# SCH_NERC_2025-07-13.net
KiCad netlist of a schematic drawn in EasyEDA
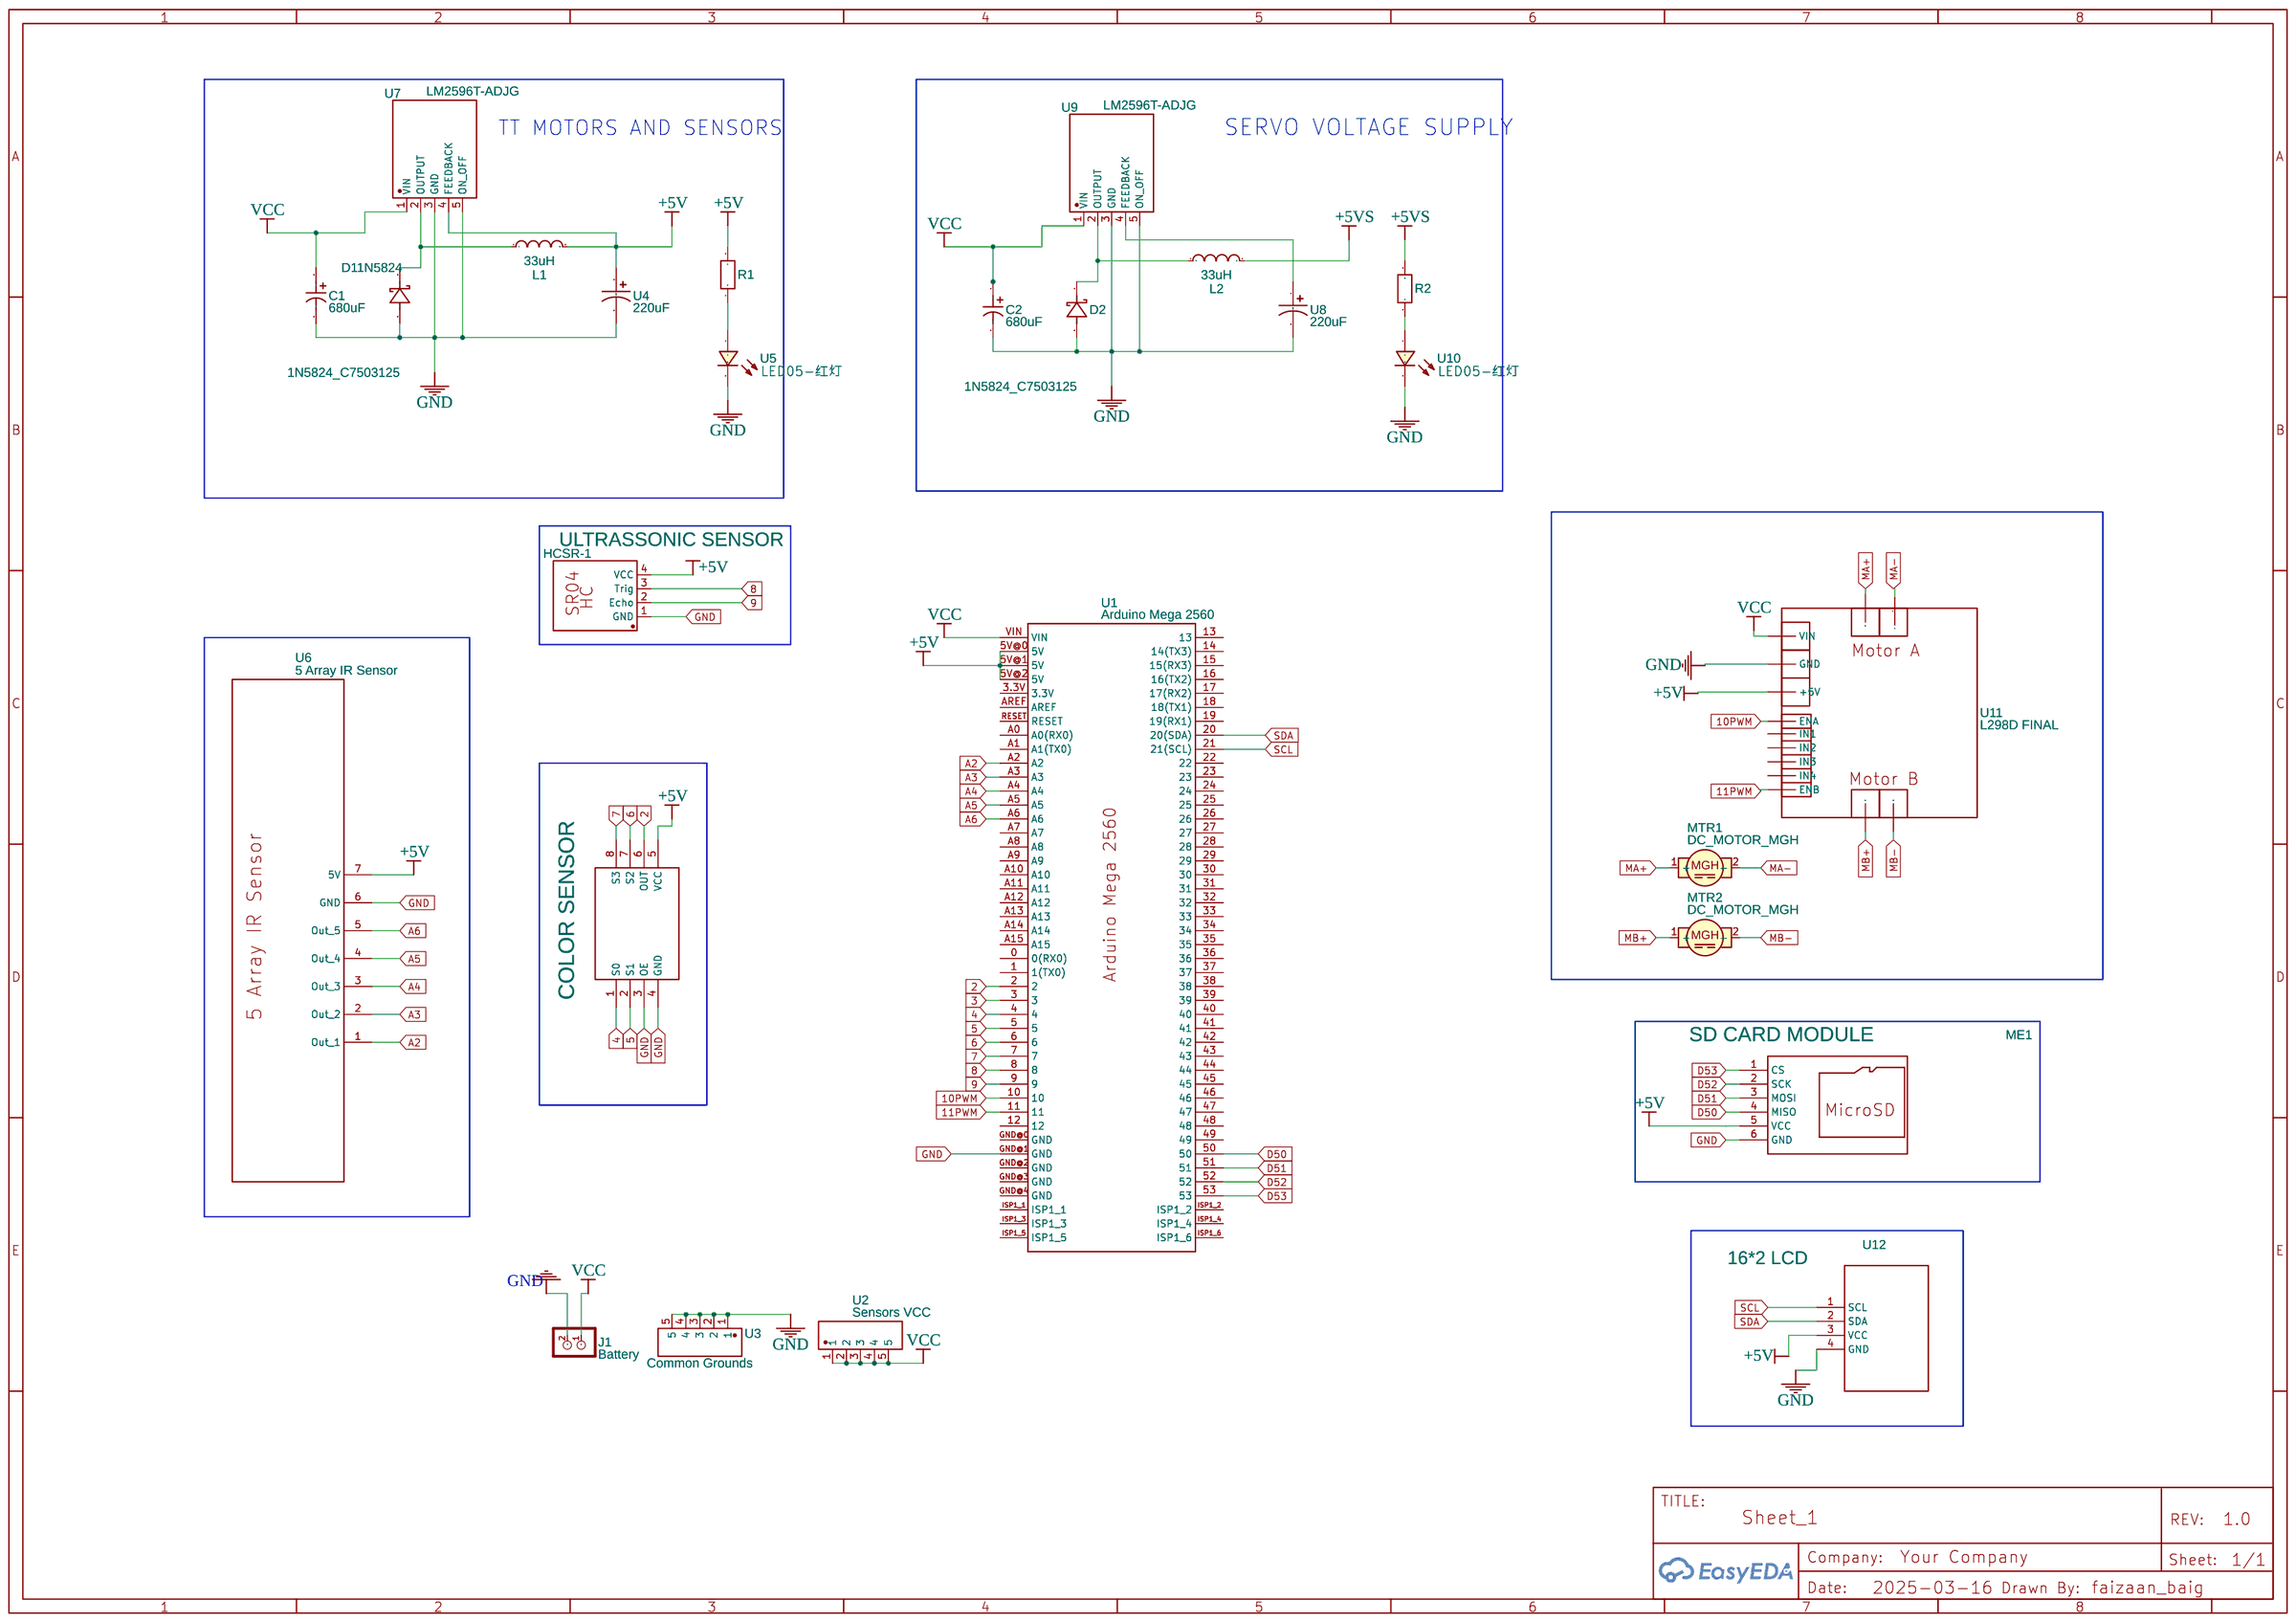
[diagram p0: schematic sheet]

(export (version "E")
  (design (tool "Eeschema 10.0.6"))
  (components
    (comp (ref "C1")
      (value "680uF")
      (fields
        (field (name "Manufacturer Part") "22UF400V87EC0285")
        (field (name "Manufacturer") "KNSCHA(科尼盛)")
      )
      (libsource (lib "") (part "22UF400V87EC0285"))
    )
    (comp (ref "C2")
      (value "680uF")
      (fields
        (field (name "Manufacturer Part") "22UF400V87EC0285")
        (field (name "Manufacturer") "KNSCHA(科尼盛)")
      )
      (libsource (lib "") (part "22UF400V87EC0285_1"))
    )
    (comp (ref "D2")
      (value "1N5824_C7503125")
      (fields (field (name "Manufacturer Part") "1N5824") (field (name "Manufacturer") "FUXINSEMI(富芯森美)"))
      (libsource (lib "") (part "1N5824_C7503125"))
    )
    (comp (ref "D11N5824")
      (value "1N5824_C7503125")
      (fields (field (name "Manufacturer Part") "1N5824") (field (name "Manufacturer") "FUXINSEMI(富芯森美)"))
      (libsource (lib "") (part "1N5824_C7503125_1"))
    )
    (comp (ref "HCSR-1") (value "ULTRASSONIC SENSOR") (libsource (lib "") (part "ULTRASSONIC SENSOR COPY")))
    (comp (ref "J1") (value "Battery") (libsource (lib "") (part "CON_TERMINAL_BLOCK_02-5MM")))
    (comp (ref "L1")
      (value "33uH")
      (fields (field (name "Manufacturer Part") "CKCS5040-33uH/M") (field (name "Manufacturer") "CENKER(岑科)"))
      (libsource (lib "") (part "CKCS5040-33UH/M_1"))
    )
    (comp (ref "L2")
      (value "33uH")
      (fields (field (name "Manufacturer Part") "CKCS5040-33uH/M") (field (name "Manufacturer") "CENKER(岑科)"))
      (libsource (lib "") (part "CKCS5040-33UH/M"))
    )
    (comp (ref "ME1")
      (value "SD CARD MODULE")
      (libsource (lib "") (part "CATALEX_MICRO_SD_CARD_MODULE_V1 SURYA"))
    )
    (comp (ref "MTR1") (value "DC_MOTOR_MGH") (libsource (lib "") (part "DC_MOTOR_MGH")))
    (comp (ref "MTR2") (value "DC_MOTOR_MGH") (libsource (lib "") (part "DC_MOTOR_MGH")))
    (comp (ref "R1")
      (value "贴片电阻CHIPRESISTORS")
      (fields (field (name "Manufacturer Part") "贴片电阻ChipResistors"))
      (libsource (lib "") (part "贴片电阻CHIPRESISTORS"))
    )
    (comp (ref "R2")
      (value "贴片电阻CHIPRESISTORS")
      (fields (field (name "Manufacturer Part") "贴片电阻ChipResistors"))
      (libsource (lib "") (part "贴片电阻CHIPRESISTORS"))
    )
    (comp (ref "SENSOR1") (value "COLOR SENSOR") (libsource (lib "") (part "COLOR SENSOR")))
    (comp (ref "U1") (value "Arduino Mega 2560") (libsource (lib "") (part "Arduino Mega 2560")))
    (comp (ref "U2")
      (value "Sensors VCC")
      (fields (field (name "Manufacturer Part") "HDR-1X5插件"))
      (libsource (lib "") (part "HDR-1X5."))
    )
    (comp (ref "U3")
      (value "Common Grounds")
      (fields (field (name "Manufacturer Part") "HDR-1X5插件"))
      (libsource (lib "") (part "HDR-1X5._1"))
    )
    (comp (ref "U4")
      (value "220uF")
      (fields
        (field (name "Manufacturer Part") "16YK220M6.3X11")
        (field (name "Manufacturer") "rubycon(红宝石)")
      )
      (libsource (lib "") (part "16YK220M6.3X11"))
    )
    (comp (ref "U5") (value "LED05-红灯") (libsource (lib "") (part "LED05-红灯")))
    (comp (ref "U6") (value "5 Array IR Sensor") (libsource (lib "") (part "5 Array IR Sensor")))
    (comp (ref "U7")
      (value "LM2596T-ADJG")
      (fields (field (name "Manufacturer") "HGC(深圳汉芯)"))
      (libsource (lib "") (part "LM2596T-ADJG"))
    )
    (comp (ref "U8")
      (value "220uF")
      (fields
        (field (name "Manufacturer Part") "16YK220M6.3X11")
        (field (name "Manufacturer") "rubycon(红宝石)")
      )
      (libsource (lib "") (part "16YK220M6.3X11"))
    )
    (comp (ref "U9")
      (value "LM2596T-ADJG")
      (fields (field (name "Manufacturer") "HGC(深圳汉芯)"))
      (libsource (lib "") (part "LM2596T-ADJG"))
    )
    (comp (ref "U10") (value "LED05-红灯") (libsource (lib "") (part "LED05-红灯")))
    (comp (ref "U11") (value "L298D FINAL") (libsource (lib "") (part "L298D FINAL")))
    (comp (ref "U12") (value "16*2 LCD") (libsource (lib "") (part "Grove - I2C ADC")))
  )
  (nets
    (net (code "1") (name "+5V") (class "Default")
      (node (ref "HCSR-1") (pin "4") (pinfunction "VCC_4") (pintype "unspecified"))
      (node (ref "L1") (pin "2") (pinfunction "2_2") (pintype "unspecified"))
      (node (ref "ME1") (pin "5") (pinfunction "VCC_5") (pintype "unspecified"))
      (node (ref "R1") (pin "2") (pinfunction "2_2") (pintype "unspecified"))
      (node (ref "SENSOR1") (pin "5") (pinfunction "VCC_5") (pintype "unspecified"))
      (node (ref "U1") (pin "5V@0") (pinfunction "5V_5V@0") (pintype "unspecified"))
      (node (ref "U1") (pin "5V@1") (pinfunction "5V_5V@1") (pintype "unspecified"))
      (node (ref "U1") (pin "5V@2") (pinfunction "5V_5V@2") (pintype "unspecified"))
      (node (ref "U11") (pin "13") (pinfunction "+5V_13") (pintype "unspecified"))
      (node (ref "U12") (pin "3") (pinfunction "VCC_3") (pintype "unspecified"))
      (node (ref "U4") (pin "1") (pinfunction "1_1") (pintype "unspecified"))
      (node (ref "U6") (pin "7") (pinfunction "5V_7") (pintype "unspecified"))
      (node (ref "U7") (pin "4") (pinfunction "FEEDBACK_4") (pintype "unspecified"))
    )
    (net (code "2") (name "+5VS") (class "Default")
      (node (ref "L2") (pin "2") (pinfunction "2_2") (pintype "unspecified"))
      (node (ref "R2") (pin "2") (pinfunction "2_2") (pintype "unspecified"))
    )
    (net (code "3") (name "2") (class "Default")
      (node (ref "SENSOR1") (pin "6") (pinfunction "OUT_6") (pintype "unspecified"))
      (node (ref "U1") (pin "2") (pinfunction "2_2") (pintype "unspecified"))
    )
    (net (code "4") (name "3") (class "Default")
      (node (ref "U1") (pin "3") (pinfunction "3_3") (pintype "unspecified"))
    )
    (net (code "5") (name "4") (class "Default")
      (node (ref "SENSOR1") (pin "1") (pinfunction "S0_1") (pintype "unspecified"))
      (node (ref "U1") (pin "4") (pinfunction "4_4") (pintype "unspecified"))
    )
    (net (code "6") (name "5") (class "Default")
      (node (ref "SENSOR1") (pin "2") (pinfunction "S1_2") (pintype "unspecified"))
      (node (ref "U1") (pin "5") (pinfunction "5_5") (pintype "unspecified"))
    )
    (net (code "7") (name "6") (class "Default")
      (node (ref "SENSOR1") (pin "7") (pinfunction "S2_7") (pintype "unspecified"))
      (node (ref "U1") (pin "6") (pinfunction "6_6") (pintype "unspecified"))
    )
    (net (code "8") (name "7") (class "Default")
      (node (ref "SENSOR1") (pin "8") (pinfunction "S3_8") (pintype "unspecified"))
      (node (ref "U1") (pin "7") (pinfunction "7_7") (pintype "unspecified"))
    )
    (net (code "9") (name "8") (class "Default")
      (node (ref "HCSR-1") (pin "3") (pinfunction "Trig_3") (pintype "unspecified"))
      (node (ref "U1") (pin "8") (pinfunction "8_8") (pintype "unspecified"))
    )
    (net (code "10") (name "9") (class "Default")
      (node (ref "HCSR-1") (pin "2") (pinfunction "Echo_2") (pintype "unspecified"))
      (node (ref "U1") (pin "9") (pinfunction "9_9") (pintype "unspecified"))
    )
    (net (code "11") (name "10PWM") (class "Default")
      (node (ref "U1") (pin "10") (pinfunction "10_10") (pintype "unspecified"))
      (node (ref "U11") (pin "1") (pinfunction "ENA_1") (pintype "unspecified"))
    )
    (net (code "12") (name "11PWM") (class "Default")
      (node (ref "U1") (pin "11") (pinfunction "11_11") (pintype "unspecified"))
      (node (ref "U11") (pin "6") (pinfunction "ENB_6") (pintype "unspecified"))
    )
    (net (code "13") (name "A2") (class "Default")
      (node (ref "U1") (pin "A2") (pinfunction "A2_A2") (pintype "unspecified"))
      (node (ref "U6") (pin "1") (pinfunction "Out_1_1") (pintype "unspecified"))
    )
    (net (code "14") (name "A3") (class "Default")
      (node (ref "U1") (pin "A3") (pinfunction "A3_A3") (pintype "unspecified"))
      (node (ref "U6") (pin "2") (pinfunction "Out_2_2") (pintype "unspecified"))
    )
    (net (code "15") (name "A4") (class "Default")
      (node (ref "U1") (pin "A4") (pinfunction "A4_A4") (pintype "unspecified"))
      (node (ref "U6") (pin "3") (pinfunction "Out_3_3") (pintype "unspecified"))
    )
    (net (code "16") (name "A5") (class "Default")
      (node (ref "U1") (pin "A5") (pinfunction "A5_A5") (pintype "unspecified"))
      (node (ref "U6") (pin "4") (pinfunction "Out_4_4") (pintype "unspecified"))
    )
    (net (code "17") (name "A6") (class "Default")
      (node (ref "U1") (pin "A6") (pinfunction "A6_A6") (pintype "unspecified"))
      (node (ref "U6") (pin "5") (pinfunction "Out_5_5") (pintype "unspecified"))
    )
    (net (code "18") (name "D50") (class "Default")
      (node (ref "ME1") (pin "4") (pinfunction "MISO_4") (pintype "unspecified"))
      (node (ref "U1") (pin "50") (pinfunction "50_50") (pintype "unspecified"))
    )
    (net (code "19") (name "D51") (class "Default")
      (node (ref "ME1") (pin "3") (pinfunction "MOSI_3") (pintype "unspecified"))
      (node (ref "U1") (pin "51") (pinfunction "51_51") (pintype "unspecified"))
    )
    (net (code "20") (name "D52") (class "Default")
      (node (ref "ME1") (pin "2") (pinfunction "SCK_2") (pintype "unspecified"))
      (node (ref "U1") (pin "52") (pinfunction "52_52") (pintype "unspecified"))
    )
    (net (code "21") (name "D53") (class "Default")
      (node (ref "ME1") (pin "1") (pinfunction "CS_1") (pintype "unspecified"))
      (node (ref "U1") (pin "53") (pinfunction "53_53") (pintype "unspecified"))
    )
    (net (code "22") (name "GND") (class "Default")
      (node (ref "C1") (pin "2") (pinfunction "2_2") (pintype "input"))
      (node (ref "C2") (pin "2") (pinfunction "2_2") (pintype "input"))
      (node (ref "D11N5824") (pin "2") (pinfunction "A_2") (pintype "unspecified"))
      (node (ref "D2") (pin "2") (pinfunction "A_2") (pintype "unspecified"))
      (node (ref "HCSR-1") (pin "1") (pinfunction "GND_1") (pintype "unspecified"))
      (node (ref "J1") (pin "2") (pinfunction "2_2") (pintype "unspecified"))
      (node (ref "ME1") (pin "6") (pinfunction "GND_6") (pintype "unspecified"))
      (node (ref "SENSOR1") (pin "3") (pinfunction "OE_3") (pintype "unspecified"))
      (node (ref "SENSOR1") (pin "4") (pinfunction "GND_4") (pintype "unspecified"))
      (node (ref "U1") (pin "GND@1") (pinfunction "GND_GND@1") (pintype "unspecified"))
      (node (ref "U10") (pin "2") (pinfunction "2_2") (pintype "unspecified"))
      (node (ref "U11") (pin "12") (pinfunction "GND_12") (pintype "unspecified"))
      (node (ref "U12") (pin "4") (pinfunction "GND_4") (pintype "unspecified"))
      (node (ref "U3") (pin "1") (pinfunction "1_1") (pintype "unspecified"))
      (node (ref "U3") (pin "2") (pinfunction "2_2") (pintype "unspecified"))
      (node (ref "U3") (pin "3") (pinfunction "3_3") (pintype "unspecified"))
      (node (ref "U3") (pin "4") (pinfunction "4_4") (pintype "unspecified"))
      (node (ref "U3") (pin "5") (pinfunction "5_5") (pintype "unspecified"))
      (node (ref "U4") (pin "2") (pinfunction "2_2") (pintype "unspecified"))
      (node (ref "U5") (pin "2") (pinfunction "2_2") (pintype "unspecified"))
      (node (ref "U6") (pin "6") (pinfunction "GND_6") (pintype "unspecified"))
      (node (ref "U7") (pin "3") (pinfunction "GND_3") (pintype "unspecified"))
      (node (ref "U7") (pin "5") (pinfunction "ON_OFF_5") (pintype "unspecified"))
      (node (ref "U8") (pin "2") (pinfunction "2_2") (pintype "unspecified"))
      (node (ref "U9") (pin "3") (pinfunction "GND_3") (pintype "unspecified"))
      (node (ref "U9") (pin "5") (pinfunction "ON_OFF_5") (pintype "unspecified"))
    )
    (net (code "23") (name "MA+") (class "Default")
      (node (ref "MTR1") (pin "1") (pinfunction "+_1") (pintype "passive"))
      (node (ref "U11") (pin "8") (pinfunction "8_8") (pintype "unspecified"))
    )
    (net (code "24") (name "MA-") (class "Default")
      (node (ref "MTR1") (pin "2") (pinfunction "-_2") (pintype "passive"))
      (node (ref "U11") (pin "7") (pinfunction "7_7") (pintype "unspecified"))
    )
    (net (code "25") (name "MB+") (class "Default")
      (node (ref "MTR2") (pin "1") (pinfunction "+_1") (pintype "passive"))
      (node (ref "U11") (pin "10") (pinfunction "10_10") (pintype "unspecified"))
    )
    (net (code "26") (name "MB-") (class "Default")
      (node (ref "MTR2") (pin "2") (pinfunction "-_2") (pintype "passive"))
      (node (ref "U11") (pin "9") (pinfunction "9_9") (pintype "unspecified"))
    )
    (net (code "27") (name "Net-(D2-K)") (class "Default")
      (node (ref "D2") (pin "1") (pinfunction "K_1") (pintype "unspecified"))
      (node (ref "L2") (pin "1") (pinfunction "1_1") (pintype "unspecified"))
      (node (ref "U9") (pin "2") (pinfunction "OUTPUT_2") (pintype "unspecified"))
    )
    (net (code "28") (name "Net-(D11N5824-K)") (class "Default")
      (node (ref "D11N5824") (pin "1") (pinfunction "K_1") (pintype "unspecified"))
      (node (ref "L1") (pin "1") (pinfunction "1_1") (pintype "unspecified"))
      (node (ref "U7") (pin "2") (pinfunction "OUTPUT_2") (pintype "unspecified"))
    )
    (net (code "29") (name "Net-(R1-Pad1)") (class "Default")
      (node (ref "R1") (pin "1") (pinfunction "1_1") (pintype "unspecified"))
      (node (ref "U5") (pin "1") (pinfunction "1_1") (pintype "unspecified"))
    )
    (net (code "30") (name "Net-(R2-Pad1)") (class "Default")
      (node (ref "R2") (pin "1") (pinfunction "1_1") (pintype "unspecified"))
      (node (ref "U10") (pin "1") (pinfunction "1_1") (pintype "unspecified"))
    )
    (net (code "31") (name "Net-(U9-FEEDBACK)") (class "Default")
      (node (ref "U8") (pin "1") (pinfunction "1_1") (pintype "unspecified"))
      (node (ref "U9") (pin "4") (pinfunction "FEEDBACK_4") (pintype "unspecified"))
    )
    (net (code "32") (name "SCL") (class "Default")
      (node (ref "U1") (pin "21") (pinfunction "21(SCL)_21") (pintype "unspecified"))
      (node (ref "U12") (pin "1") (pinfunction "SCL_1") (pintype "unspecified"))
    )
    (net (code "33") (name "SDA") (class "Default")
      (node (ref "U1") (pin "20") (pinfunction "20(SDA)_20") (pintype "unspecified"))
      (node (ref "U12") (pin "2") (pinfunction "SDA_2") (pintype "unspecified"))
    )
    (net (code "34") (name "VCC") (class "Default")
      (node (ref "C1") (pin "1") (pinfunction "1_1") (pintype "input"))
      (node (ref "C2") (pin "1") (pinfunction "1_1") (pintype "input"))
      (node (ref "J1") (pin "1") (pinfunction "1_1") (pintype "unspecified"))
      (node (ref "U1") (pin "VIN") (pinfunction "VIN_VIN") (pintype "unspecified"))
      (node (ref "U11") (pin "11") (pinfunction "VIN_11") (pintype "unspecified"))
      (node (ref "U2") (pin "1") (pinfunction "1_1") (pintype "unspecified"))
      (node (ref "U2") (pin "2") (pinfunction "2_2") (pintype "unspecified"))
      (node (ref "U2") (pin "3") (pinfunction "3_3") (pintype "unspecified"))
      (node (ref "U2") (pin "4") (pinfunction "4_4") (pintype "unspecified"))
      (node (ref "U2") (pin "5") (pinfunction "5_5") (pintype "unspecified"))
      (node (ref "U7") (pin "1") (pinfunction "VIN_1") (pintype "unspecified"))
      (node (ref "U9") (pin "1") (pinfunction "VIN_1") (pintype "unspecified"))
    )
    (net (code "35") (name "unconnected-(U1-0(RX0)-Pad0)") (class "Default")
      (node (ref "U1") (pin "0") (pinfunction "0(RX0)_0") (pintype "unspecified"))
    )
    (net (code "36") (name "unconnected-(U1-1(TX0)-Pad1)") (class "Default")
      (node (ref "U1") (pin "1") (pinfunction "1(TX0)_1") (pintype "unspecified"))
    )
    (net (code "37") (name "unconnected-(U1-14(TX3)-Pad14)") (class "Default")
      (node (ref "U1") (pin "14") (pinfunction "14(TX3)_14") (pintype "unspecified"))
    )
    (net (code "38") (name "unconnected-(U1-15(RX3)-Pad15)") (class "Default")
      (node (ref "U1") (pin "15") (pinfunction "15(RX3)_15") (pintype "unspecified"))
    )
    (net (code "39") (name "unconnected-(U1-16(TX2)-Pad16)") (class "Default")
      (node (ref "U1") (pin "16") (pinfunction "16(TX2)_16") (pintype "unspecified"))
    )
    (net (code "40") (name "unconnected-(U1-17(RX2)-Pad17)") (class "Default")
      (node (ref "U1") (pin "17") (pinfunction "17(RX2)_17") (pintype "unspecified"))
    )
    (net (code "41") (name "unconnected-(U1-18(TX1)-Pad18)") (class "Default")
      (node (ref "U1") (pin "18") (pinfunction "18(TX1)_18") (pintype "unspecified"))
    )
    (net (code "42") (name "unconnected-(U1-19(RX1)-Pad19)") (class "Default")
      (node (ref "U1") (pin "19") (pinfunction "19(RX1)_19") (pintype "unspecified"))
    )
    (net (code "43") (name "unconnected-(U1-A0(RX0)-PadA0)") (class "Default")
      (node (ref "U1") (pin "A0") (pinfunction "A0(RX0)_A0") (pintype "unspecified"))
    )
    (net (code "44") (name "unconnected-(U1-A1(TX0)-PadA1)") (class "Default")
      (node (ref "U1") (pin "A1") (pinfunction "A1(TX0)_A1") (pintype "unspecified"))
    )
    (net (code "45") (name "unconnected-(U1-GND-PadGND@0)") (class "Default")
      (node (ref "U1") (pin "GND@0") (pinfunction "GND_GND@0") (pintype "unspecified"))
    )
    (net (code "46") (name "unconnected-(U1-GND-PadGND@2)") (class "Default")
      (node (ref "U1") (pin "GND@2") (pinfunction "GND_GND@2") (pintype "unspecified"))
    )
    (net (code "47") (name "unconnected-(U1-GND-PadGND@3)") (class "Default")
      (node (ref "U1") (pin "GND@3") (pinfunction "GND_GND@3") (pintype "unspecified"))
    )
    (net (code "48") (name "unconnected-(U1-GND-PadGND@4)") (class "Default")
      (node (ref "U1") (pin "GND@4") (pinfunction "GND_GND@4") (pintype "unspecified"))
    )
    (net (code "49") (name "unconnected-(U1-Pad3.3V)") (class "Default")
      (node (ref "U1") (pin "3.3V") (pinfunction "3.3V_3.3V") (pintype "unspecified"))
    )
    (net (code "50") (name "unconnected-(U1-Pad12)") (class "Default")
      (node (ref "U1") (pin "12") (pinfunction "12_12") (pintype "unspecified"))
    )
    (net (code "51") (name "unconnected-(U1-Pad13)") (class "Default")
      (node (ref "U1") (pin "13") (pinfunction "13_13") (pintype "unspecified"))
    )
    (net (code "52") (name "unconnected-(U1-Pad22)") (class "Default")
      (node (ref "U1") (pin "22") (pinfunction "22_22") (pintype "unspecified"))
    )
    (net (code "53") (name "unconnected-(U1-Pad23)") (class "Default")
      (node (ref "U1") (pin "23") (pinfunction "23_23") (pintype "unspecified"))
    )
    (net (code "54") (name "unconnected-(U1-Pad24)") (class "Default")
      (node (ref "U1") (pin "24") (pinfunction "24_24") (pintype "unspecified"))
    )
    (net (code "55") (name "unconnected-(U1-Pad25)") (class "Default")
      (node (ref "U1") (pin "25") (pinfunction "25_25") (pintype "unspecified"))
    )
    (net (code "56") (name "unconnected-(U1-Pad26)") (class "Default")
      (node (ref "U1") (pin "26") (pinfunction "26_26") (pintype "unspecified"))
    )
    (net (code "57") (name "unconnected-(U1-Pad27)") (class "Default")
      (node (ref "U1") (pin "27") (pinfunction "27_27") (pintype "unspecified"))
    )
    (net (code "58") (name "unconnected-(U1-Pad28)") (class "Default")
      (node (ref "U1") (pin "28") (pinfunction "28_28") (pintype "unspecified"))
    )
    (net (code "59") (name "unconnected-(U1-Pad29)") (class "Default")
      (node (ref "U1") (pin "29") (pinfunction "29_29") (pintype "unspecified"))
    )
    (net (code "60") (name "unconnected-(U1-Pad30)") (class "Default")
      (node (ref "U1") (pin "30") (pinfunction "30_30") (pintype "unspecified"))
    )
    (net (code "61") (name "unconnected-(U1-Pad31)") (class "Default")
      (node (ref "U1") (pin "31") (pinfunction "31_31") (pintype "unspecified"))
    )
    (net (code "62") (name "unconnected-(U1-Pad32)") (class "Default")
      (node (ref "U1") (pin "32") (pinfunction "32_32") (pintype "unspecified"))
    )
    (net (code "63") (name "unconnected-(U1-Pad33)") (class "Default")
      (node (ref "U1") (pin "33") (pinfunction "33_33") (pintype "unspecified"))
    )
    (net (code "64") (name "unconnected-(U1-Pad34)") (class "Default")
      (node (ref "U1") (pin "34") (pinfunction "34_34") (pintype "unspecified"))
    )
    (net (code "65") (name "unconnected-(U1-Pad35)") (class "Default")
      (node (ref "U1") (pin "35") (pinfunction "35_35") (pintype "unspecified"))
    )
    (net (code "66") (name "unconnected-(U1-Pad36)") (class "Default")
      (node (ref "U1") (pin "36") (pinfunction "36_36") (pintype "unspecified"))
    )
    (net (code "67") (name "unconnected-(U1-Pad37)") (class "Default")
      (node (ref "U1") (pin "37") (pinfunction "37_37") (pintype "unspecified"))
    )
    (net (code "68") (name "unconnected-(U1-Pad38)") (class "Default")
      (node (ref "U1") (pin "38") (pinfunction "38_38") (pintype "unspecified"))
    )
    (net (code "69") (name "unconnected-(U1-Pad39)") (class "Default")
      (node (ref "U1") (pin "39") (pinfunction "39_39") (pintype "unspecified"))
    )
    (net (code "70") (name "unconnected-(U1-Pad40)") (class "Default")
      (node (ref "U1") (pin "40") (pinfunction "40_40") (pintype "unspecified"))
    )
    (net (code "71") (name "unconnected-(U1-Pad41)") (class "Default")
      (node (ref "U1") (pin "41") (pinfunction "41_41") (pintype "unspecified"))
    )
    (net (code "72") (name "unconnected-(U1-Pad42)") (class "Default")
      (node (ref "U1") (pin "42") (pinfunction "42_42") (pintype "unspecified"))
    )
    (net (code "73") (name "unconnected-(U1-Pad43)") (class "Default")
      (node (ref "U1") (pin "43") (pinfunction "43_43") (pintype "unspecified"))
    )
    (net (code "74") (name "unconnected-(U1-Pad44)") (class "Default")
      (node (ref "U1") (pin "44") (pinfunction "44_44") (pintype "unspecified"))
    )
    (net (code "75") (name "unconnected-(U1-Pad45)") (class "Default")
      (node (ref "U1") (pin "45") (pinfunction "45_45") (pintype "unspecified"))
    )
    (net (code "76") (name "unconnected-(U1-Pad46)") (class "Default")
      (node (ref "U1") (pin "46") (pinfunction "46_46") (pintype "unspecified"))
    )
    (net (code "77") (name "unconnected-(U1-Pad47)") (class "Default")
      (node (ref "U1") (pin "47") (pinfunction "47_47") (pintype "unspecified"))
    )
    (net (code "78") (name "unconnected-(U1-Pad48)") (class "Default")
      (node (ref "U1") (pin "48") (pinfunction "48_48") (pintype "unspecified"))
    )
    (net (code "79") (name "unconnected-(U1-Pad49)") (class "Default")
      (node (ref "U1") (pin "49") (pinfunction "49_49") (pintype "unspecified"))
    )
    (net (code "80") (name "unconnected-(U1-PadA7)") (class "Default")
      (node (ref "U1") (pin "A7") (pinfunction "A7_A7") (pintype "unspecified"))
    )
    (net (code "81") (name "unconnected-(U1-PadA8)") (class "Default")
      (node (ref "U1") (pin "A8") (pinfunction "A8_A8") (pintype "unspecified"))
    )
    (net (code "82") (name "unconnected-(U1-PadA9)") (class "Default")
      (node (ref "U1") (pin "A9") (pinfunction "A9_A9") (pintype "unspecified"))
    )
    (net (code "83") (name "unconnected-(U1-PadA10)") (class "Default")
      (node (ref "U1") (pin "A10") (pinfunction "A10_A10") (pintype "unspecified"))
    )
    (net (code "84") (name "unconnected-(U1-PadA11)") (class "Default")
      (node (ref "U1") (pin "A11") (pinfunction "A11_A11") (pintype "unspecified"))
    )
    (net (code "85") (name "unconnected-(U1-PadA12)") (class "Default")
      (node (ref "U1") (pin "A12") (pinfunction "A12_A12") (pintype "unspecified"))
    )
    (net (code "86") (name "unconnected-(U1-PadA13)") (class "Default")
      (node (ref "U1") (pin "A13") (pinfunction "A13_A13") (pintype "unspecified"))
    )
    (net (code "87") (name "unconnected-(U1-PadA14)") (class "Default")
      (node (ref "U1") (pin "A14") (pinfunction "A14_A14") (pintype "unspecified"))
    )
    (net (code "88") (name "unconnected-(U1-PadA15)") (class "Default")
      (node (ref "U1") (pin "A15") (pinfunction "A15_A15") (pintype "unspecified"))
    )
    (net (code "89") (name "unconnected-(U1-PadAREF)") (class "Default")
      (node (ref "U1") (pin "AREF") (pinfunction "AREF_AREF") (pintype "unspecified"))
    )
    (net (code "90") (name "unconnected-(U1-PadISP1_1)") (class "Default")
      (node (ref "U1") (pin "ISP1_1") (pinfunction "ISP1_1_ISP1_1") (pintype "unspecified"))
    )
    (net (code "91") (name "unconnected-(U1-PadISP1_2)") (class "Default")
      (node (ref "U1") (pin "ISP1_2") (pinfunction "ISP1_2_ISP1_2") (pintype "unspecified"))
    )
    (net (code "92") (name "unconnected-(U1-PadISP1_3)") (class "Default")
      (node (ref "U1") (pin "ISP1_3") (pinfunction "ISP1_3_ISP1_3") (pintype "unspecified"))
    )
    (net (code "93") (name "unconnected-(U1-PadISP1_4)") (class "Default")
      (node (ref "U1") (pin "ISP1_4") (pinfunction "ISP1_4_ISP1_4") (pintype "unspecified"))
    )
    (net (code "94") (name "unconnected-(U1-PadISP1_5)") (class "Default")
      (node (ref "U1") (pin "ISP1_5") (pinfunction "ISP1_5_ISP1_5") (pintype "unspecified"))
    )
    (net (code "95") (name "unconnected-(U1-PadISP1_6)") (class "Default")
      (node (ref "U1") (pin "ISP1_6") (pinfunction "ISP1_6_ISP1_6") (pintype "unspecified"))
    )
    (net (code "96") (name "unconnected-(U1-PadRESET)") (class "Default")
      (node (ref "U1") (pin "RESET") (pinfunction "RESET_RESET") (pintype "unspecified"))
    )
    (net (code "97") (name "unconnected-(U11-IN1-Pad2)") (class "Default")
      (node (ref "U11") (pin "2") (pinfunction "IN1_2") (pintype "unspecified"))
    )
    (net (code "98") (name "unconnected-(U11-IN2-Pad3)") (class "Default")
      (node (ref "U11") (pin "3") (pinfunction "IN2_3") (pintype "unspecified"))
    )
    (net (code "99") (name "unconnected-(U11-IN3-Pad4)") (class "Default")
      (node (ref "U11") (pin "4") (pinfunction "IN3_4") (pintype "unspecified"))
    )
    (net (code "100") (name "unconnected-(U11-IN4-Pad5)") (class "Default")
      (node (ref "U11") (pin "5") (pinfunction "IN4_5") (pintype "unspecified"))
    )
  )
)
